# LR3.net
KiCad netlist of a schematic drawn in EasyEDA
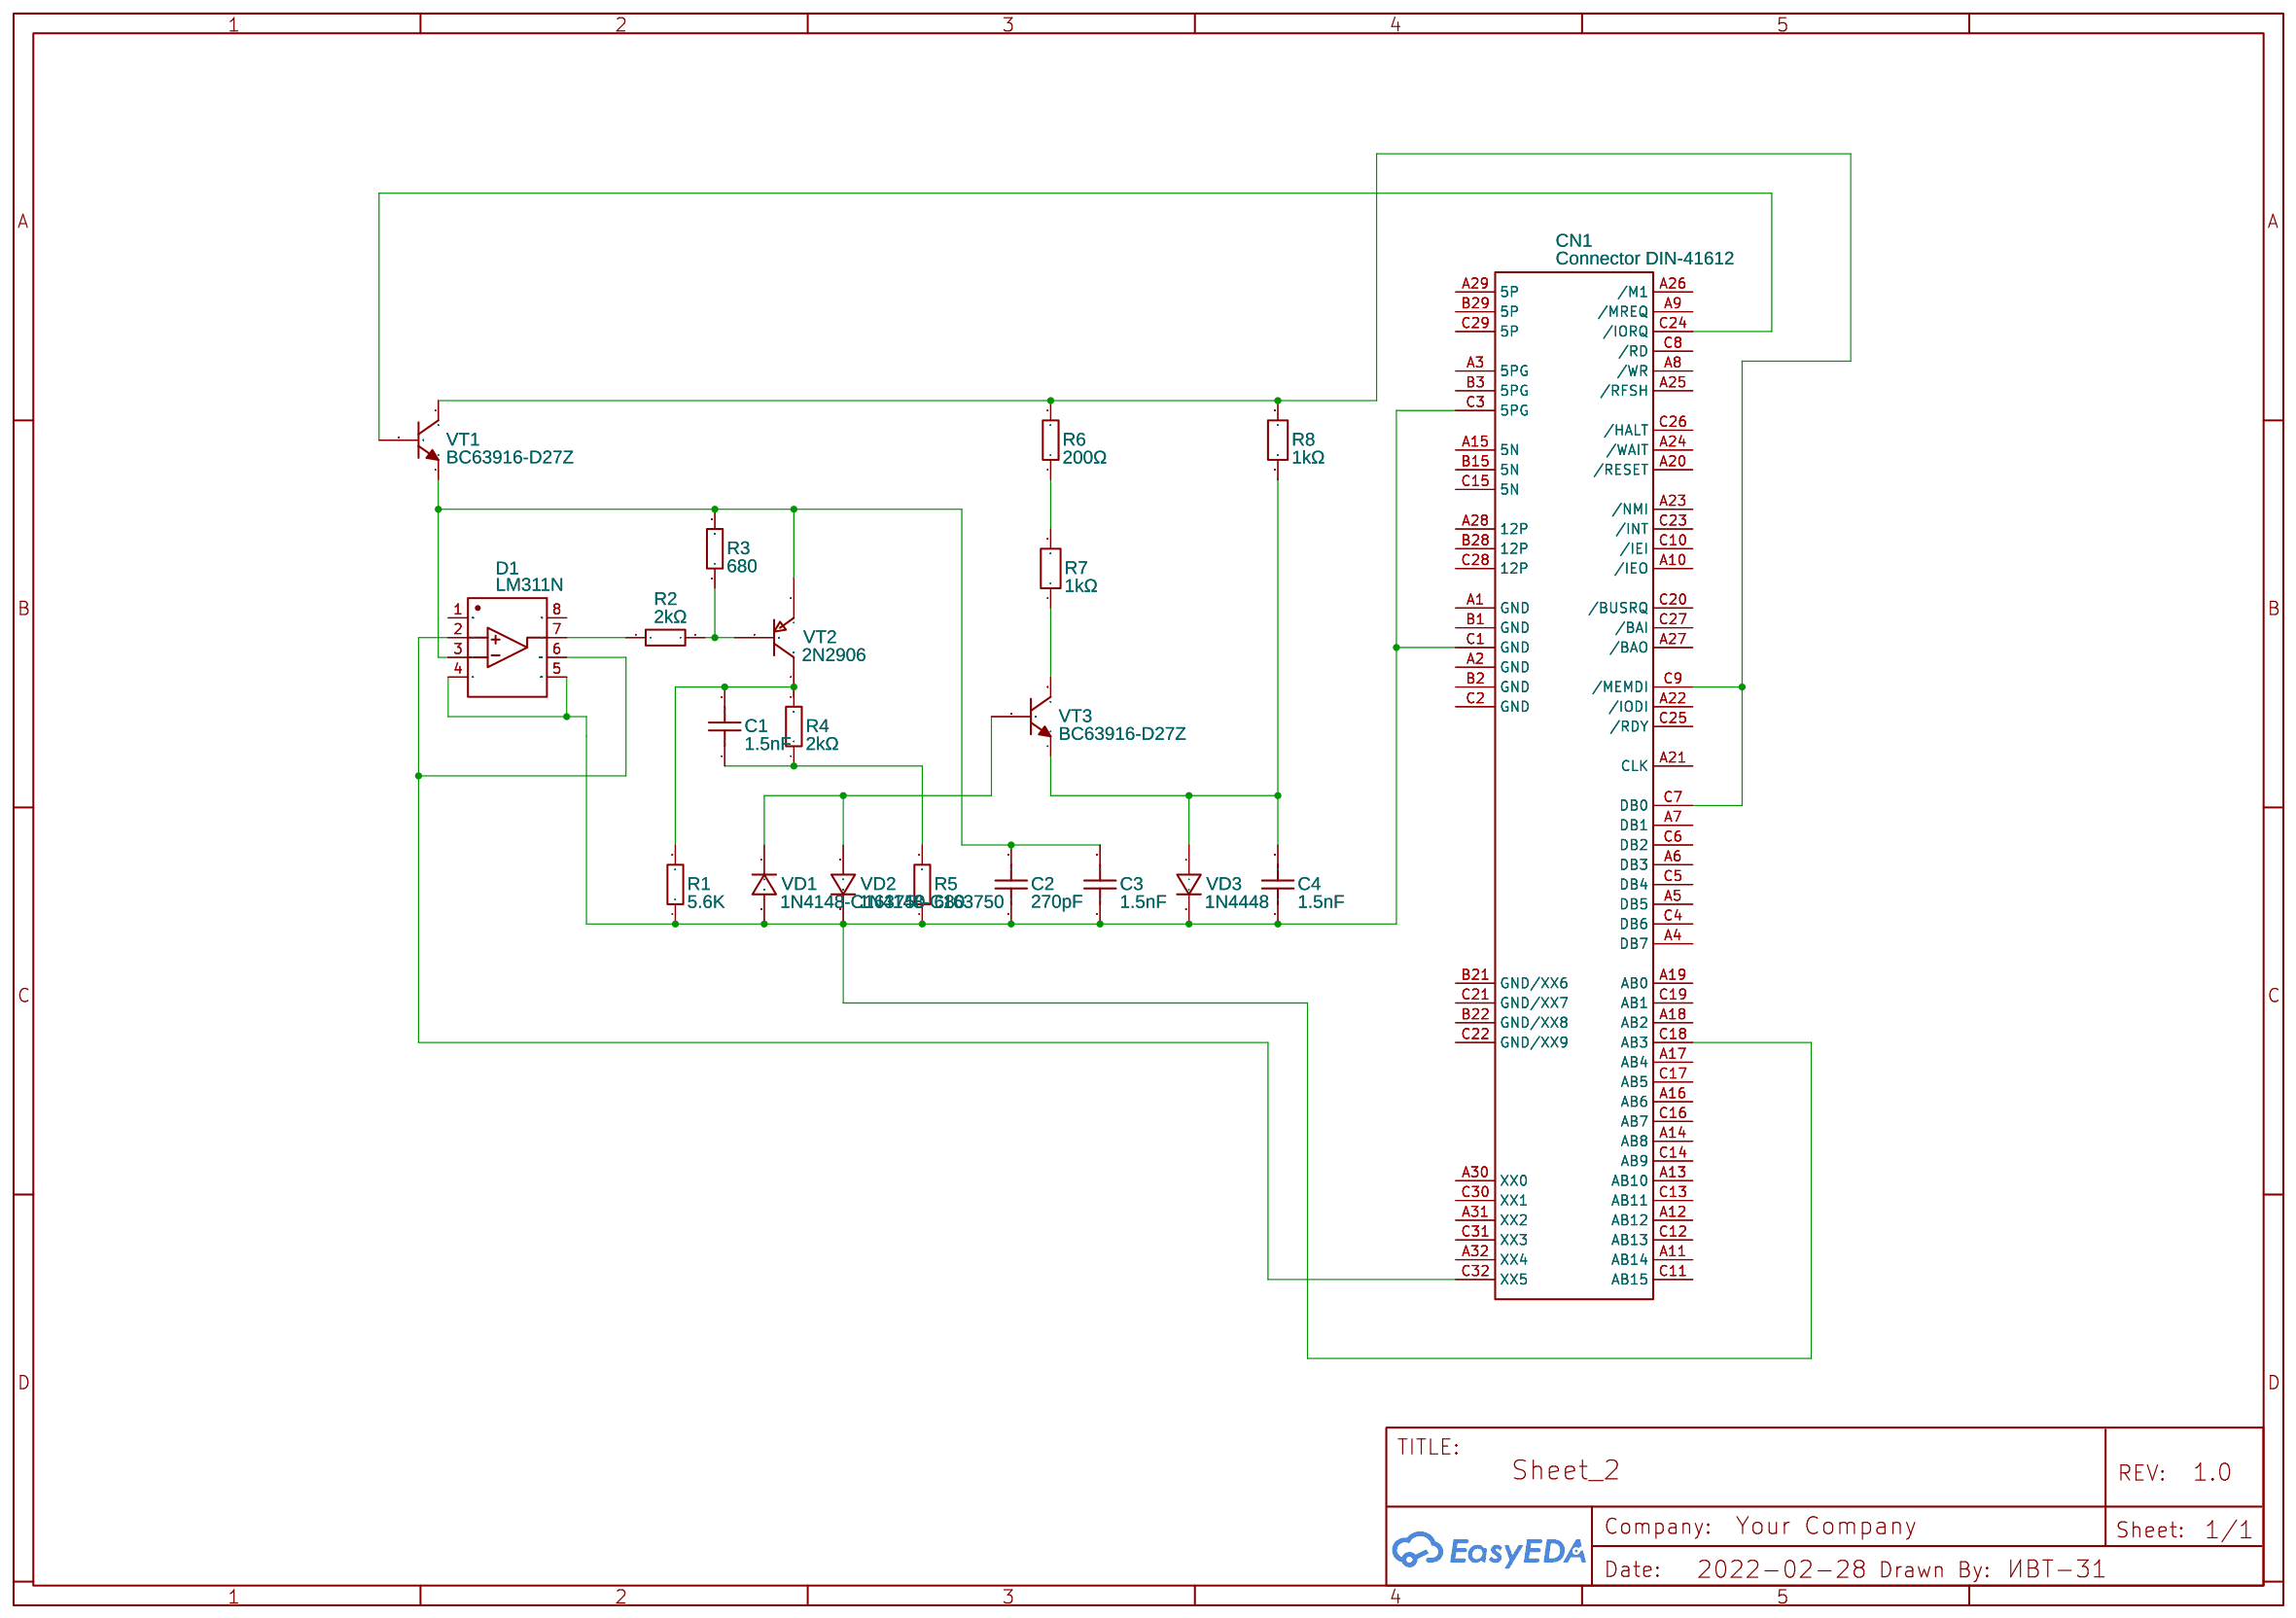
[diagram p0: schematic sheet]

(export (version "E")
  (design (tool "Eeschema 10.0.6"))
  (components
    (comp (ref "C1")
      (value "1.5nF")
      (fields
        (field (name "BOM_Manufacturer Part") "CK45-B3AD152KYVNA")
        (field (name "BOM_Supplier Part") "C342400")
      )
      (libsource (lib "") (part "CK45-B3AD152KYVNA"))
    )
    (comp (ref "C2")
      (value "270pF")
      (fields
        (field (name "BOM_Manufacturer Part") "CC1H271KC74DB44B10MN")
        (field (name "BOM_Supplier Part") "C254100")
      )
      (libsource (lib "") (part "CC1H271KC74DB44B10MN"))
    )
    (comp (ref "C3")
      (value "1.5nF")
      (fields
        (field (name "BOM_Manufacturer Part") "CK45-B3AD152KYVNA")
        (field (name "BOM_Supplier Part") "C342400")
      )
      (libsource (lib "") (part "CK45-B3AD152KYVNA"))
    )
    (comp (ref "C4")
      (value "1.5nF")
      (fields
        (field (name "BOM_Manufacturer Part") "CK45-B3AD152KYVNA")
        (field (name "BOM_Supplier Part") "C342400")
      )
      (libsource (lib "") (part "CK45-B3AD152KYVNA"))
    )
    (comp (ref "CN1")
      (value "Connector DIN-41612")
      (fields (field (name "BOM_Manufacturer Part") "EFS87"))
      (libsource (lib "") (part "Connector DIN-41612"))
    )
    (comp (ref "D1")
      (value "LM311N")
      (fields (field (name "BOM_Supplier Part") "C434572"))
      (libsource (lib "") (part "LM311N"))
    )
    (comp (ref "R1")
      (value "5.6K")
      (fields
        (field (name "BOM_Manufacturer Part") "RC0402JR-075K6L")
        (field (name "BOM_Supplier Part") "C137856")
      )
      (libsource (lib "") (part "RC0402JR-075K6L"))
    )
    (comp (ref "R2")
      (value "2kΩ")
      (fields
        (field (name "BOM_Manufacturer Part") "0603WAF2001T5E")
        (field (name "BOM_Supplier Part") "C22975")
      )
      (libsource (lib "") (part "0603WAF2001T5E_1"))
    )
    (comp (ref "R3")
      (value "680")
      (fields
        (field (name "BOM_Manufacturer Part") "RC0402JR-07680RL")
        (field (name "BOM_Supplier Part") "C137849")
      )
      (libsource (lib "") (part "RC0402JR-07680RL"))
    )
    (comp (ref "R4")
      (value "2kΩ")
      (fields
        (field (name "BOM_Manufacturer Part") "0603WAF2001T5E")
        (field (name "BOM_Supplier Part") "C22975")
      )
      (libsource (lib "") (part "0603WAF2001T5E"))
    )
    (comp (ref "R5")
      (value "680")
      (fields
        (field (name "BOM_Manufacturer Part") "RC0402JR-07680RL")
        (field (name "BOM_Supplier Part") "C137849")
      )
      (libsource (lib "") (part "RC0402JR-07680RL"))
    )
    (comp (ref "R6")
      (value "200Ω")
      (fields
        (field (name "BOM_Manufacturer Part") "RTT06201JTP")
        (field (name "BOM_Supplier Part") "C104688")
      )
      (libsource (lib "") (part "RTT06201JTP"))
    )
    (comp (ref "R7")
      (value "1kΩ")
      (fields
        (field (name "BOM_Manufacturer Part") "AS05W2J0102T5E")
        (field (name "BOM_Supplier Part") "C560481")
      )
      (libsource (lib "") (part "AS05W2J0102T5E"))
    )
    (comp (ref "R8")
      (value "1kΩ")
      (fields
        (field (name "BOM_Manufacturer Part") "AS05W2J0102T5E")
        (field (name "BOM_Supplier Part") "C560481")
      )
      (libsource (lib "") (part "AS05W2J0102T5E"))
    )
    (comp (ref "VD1")
      (value "1N4148-C163750")
      (fields (field (name "BOM_Manufacturer Part") "1N4148") (field (name "BOM_Supplier Part") "C163750"))
      (libsource (lib "") (part "1N4148-C163750"))
    )
    (comp (ref "VD2")
      (value "1N4148-C163750")
      (fields (field (name "BOM_Manufacturer Part") "1N4148") (field (name "BOM_Supplier Part") "C163750"))
      (libsource (lib "") (part "1N4148-C163750_1"))
    )
    (comp (ref "VD3")
      (value "1N4448")
      (fields (field (name "BOM_Supplier Part") "C54037"))
      (libsource (lib "") (part "1N4448"))
    )
    (comp (ref "VT1")
      (value "BC63916-D27Z")
      (fields (field (name "BOM_Supplier Part") "C900812"))
      (libsource (lib "") (part "BC63916-D27Z"))
    )
    (comp (ref "VT2") (value "2N2906") (libsource (lib "") (part "2N2906")))
    (comp (ref "VT3")
      (value "BC63916-D27Z")
      (fields (field (name "BOM_Supplier Part") "C900812"))
      (libsource (lib "") (part "BC63916-D27Z"))
    )
  )
  (nets
    (net (code "1") (name "Net-(C1-Pad1)") (class "Default")
      (node (ref "C1") (pin "1") (pinfunction "1_1") (pintype "unspecified"))
      (node (ref "R4") (pin "1") (pinfunction "1_1") (pintype "input"))
      (node (ref "R5") (pin "2") (pinfunction "2_2") (pintype "input"))
    )
    (net (code "2") (name "Net-(C1-Pad2)") (class "Default")
      (node (ref "C1") (pin "2") (pinfunction "2_2") (pintype "unspecified"))
      (node (ref "R1") (pin "2") (pinfunction "2_2") (pintype "input"))
      (node (ref "R4") (pin "2") (pinfunction "2_2") (pintype "input"))
    )
    (net (code "3") (name "Net-(CN1-AB3)") (class "Default")
      (node (ref "C2") (pin "1") (pinfunction "1_1") (pintype "unspecified"))
      (node (ref "C3") (pin "1") (pinfunction "1_1") (pintype "unspecified"))
      (node (ref "C4") (pin "1") (pinfunction "1_1") (pintype "unspecified"))
      (node (ref "CN1") (pin "C1") (pinfunction "GND_C1") (pintype "unspecified"))
      (node (ref "CN1") (pin "C18") (pinfunction "AB3_C18") (pintype "unspecified"))
      (node (ref "CN1") (pin "C3") (pinfunction "5PG_C3") (pintype "unspecified"))
      (node (ref "D1") (pin "4") (pinfunction "VEE_4") (pintype "unspecified"))
      (node (ref "D1") (pin "5") (pinfunction "BALANCE_5") (pintype "unspecified"))
      (node (ref "R1") (pin "1") (pinfunction "1_1") (pintype "input"))
      (node (ref "R5") (pin "1") (pinfunction "1_1") (pintype "input"))
      (node (ref "VD1") (pin "2") (pinfunction "2_2") (pintype "unspecified"))
      (node (ref "VD2") (pin "1") (pinfunction "1_1") (pintype "unspecified"))
      (node (ref "VD3") (pin "2") (pinfunction "K_2") (pintype "unspecified"))
    )
    (net (code "4") (name "Net-(CN1-DB0)") (class "Default")
      (node (ref "CN1") (pin "C7") (pinfunction "DB0_C7") (pintype "unspecified"))
      (node (ref "CN1") (pin "C9") (pinfunction "/MEMDI_C9") (pintype "unspecified"))
      (node (ref "R6") (pin "2") (pinfunction "2_2") (pintype "input"))
      (node (ref "R8") (pin "2") (pinfunction "2_2") (pintype "unspecified"))
      (node (ref "VT1") (pin "2") (pinfunction "C_2") (pintype "unspecified"))
    )
    (net (code "5") (name "Net-(CN1-XX5)") (class "Default")
      (node (ref "CN1") (pin "C32") (pinfunction "XX5_C32") (pintype "unspecified"))
      (node (ref "D1") (pin "2") (pinfunction "IN+_2") (pintype "unspecified"))
      (node (ref "D1") (pin "6") (pinfunction "BALANCE/STROBE_6") (pintype "unspecified"))
    )
    (net (code "6") (name "Net-(CN1-{slash}IORQ)") (class "Default")
      (node (ref "CN1") (pin "C24") (pinfunction "/IORQ_C24") (pintype "unspecified"))
      (node (ref "VT1") (pin "3") (pinfunction "B_3") (pintype "unspecified"))
    )
    (net (code "7") (name "Net-(D1-IN-)") (class "Default")
      (node (ref "C2") (pin "2") (pinfunction "2_2") (pintype "unspecified"))
      (node (ref "C3") (pin "2") (pinfunction "2_2") (pintype "unspecified"))
      (node (ref "D1") (pin "3") (pinfunction "IN-_3") (pintype "unspecified"))
      (node (ref "R3") (pin "2") (pinfunction "2_2") (pintype "input"))
      (node (ref "VT1") (pin "1") (pinfunction "E_1") (pintype "unspecified"))
      (node (ref "VT2") (pin "1") (pinfunction "E_1") (pintype "unspecified"))
    )
    (net (code "8") (name "Net-(D1-OUT)") (class "Default")
      (node (ref "D1") (pin "7") (pinfunction "OUT_7") (pintype "unspecified"))
      (node (ref "R2") (pin "1") (pinfunction "1_1") (pintype "input"))
    )
    (net (code "9") (name "Net-(R6-Pad1)") (class "Default")
      (node (ref "R6") (pin "1") (pinfunction "1_1") (pintype "input"))
      (node (ref "R7") (pin "2") (pinfunction "2_2") (pintype "unspecified"))
    )
    (net (code "10") (name "Net-(VD3-A)") (class "Default")
      (node (ref "C4") (pin "2") (pinfunction "2_2") (pintype "unspecified"))
      (node (ref "R8") (pin "1") (pinfunction "1_1") (pintype "unspecified"))
      (node (ref "VD3") (pin "1") (pinfunction "A_1") (pintype "unspecified"))
      (node (ref "VT3") (pin "1") (pinfunction "E_1") (pintype "unspecified"))
    )
    (net (code "11") (name "Net-(VT2-B)") (class "Default")
      (node (ref "R2") (pin "2") (pinfunction "2_2") (pintype "input"))
      (node (ref "R3") (pin "1") (pinfunction "1_1") (pintype "input"))
      (node (ref "VT2") (pin "2") (pinfunction "B_2") (pintype "unspecified"))
    )
    (net (code "12") (name "Net-(VT3-B)") (class "Default")
      (node (ref "VD1") (pin "1") (pinfunction "1_1") (pintype "unspecified"))
      (node (ref "VD2") (pin "2") (pinfunction "2_2") (pintype "unspecified"))
      (node (ref "VT3") (pin "3") (pinfunction "B_3") (pintype "unspecified"))
    )
    (net (code "13") (name "Net-(VT3-C)") (class "Default")
      (node (ref "R7") (pin "1") (pinfunction "1_1") (pintype "unspecified"))
      (node (ref "VT3") (pin "2") (pinfunction "C_2") (pintype "unspecified"))
    )
    (net (code "14") (name "unconnected-(CN1-5N-PadA15)") (class "Default")
      (node (ref "CN1") (pin "A15") (pinfunction "5N_A15") (pintype "unspecified"))
    )
    (net (code "15") (name "unconnected-(CN1-5N-PadB15)") (class "Default")
      (node (ref "CN1") (pin "B15") (pinfunction "5N_B15") (pintype "unspecified"))
    )
    (net (code "16") (name "unconnected-(CN1-5N-PadC15)") (class "Default")
      (node (ref "CN1") (pin "C15") (pinfunction "5N_C15") (pintype "unspecified"))
    )
    (net (code "17") (name "unconnected-(CN1-5P-PadA29)") (class "Default")
      (node (ref "CN1") (pin "A29") (pinfunction "5P_A29") (pintype "unspecified"))
    )
    (net (code "18") (name "unconnected-(CN1-5P-PadB29)") (class "Default")
      (node (ref "CN1") (pin "B29") (pinfunction "5P_B29") (pintype "unspecified"))
    )
    (net (code "19") (name "unconnected-(CN1-5P-PadC29)") (class "Default")
      (node (ref "CN1") (pin "C29") (pinfunction "5P_C29") (pintype "unspecified"))
    )
    (net (code "20") (name "unconnected-(CN1-5PG-PadA3)") (class "Default")
      (node (ref "CN1") (pin "A3") (pinfunction "5PG_A3") (pintype "unspecified"))
    )
    (net (code "21") (name "unconnected-(CN1-5PG-PadB3)") (class "Default")
      (node (ref "CN1") (pin "B3") (pinfunction "5PG_B3") (pintype "unspecified"))
    )
    (net (code "22") (name "unconnected-(CN1-12P-PadA28)") (class "Default")
      (node (ref "CN1") (pin "A28") (pinfunction "12P_A28") (pintype "unspecified"))
    )
    (net (code "23") (name "unconnected-(CN1-12P-PadB28)") (class "Default")
      (node (ref "CN1") (pin "B28") (pinfunction "12P_B28") (pintype "unspecified"))
    )
    (net (code "24") (name "unconnected-(CN1-12P-PadC28)") (class "Default")
      (node (ref "CN1") (pin "C28") (pinfunction "12P_C28") (pintype "unspecified"))
    )
    (net (code "25") (name "unconnected-(CN1-AB0-PadA19)") (class "Default")
      (node (ref "CN1") (pin "A19") (pinfunction "AB0_A19") (pintype "unspecified"))
    )
    (net (code "26") (name "unconnected-(CN1-AB1-PadC19)") (class "Default")
      (node (ref "CN1") (pin "C19") (pinfunction "AB1_C19") (pintype "unspecified"))
    )
    (net (code "27") (name "unconnected-(CN1-AB2-PadA18)") (class "Default")
      (node (ref "CN1") (pin "A18") (pinfunction "AB2_A18") (pintype "unspecified"))
    )
    (net (code "28") (name "unconnected-(CN1-AB4-PadA17)") (class "Default")
      (node (ref "CN1") (pin "A17") (pinfunction "AB4_A17") (pintype "unspecified"))
    )
    (net (code "29") (name "unconnected-(CN1-AB5-PadC17)") (class "Default")
      (node (ref "CN1") (pin "C17") (pinfunction "AB5_C17") (pintype "unspecified"))
    )
    (net (code "30") (name "unconnected-(CN1-AB6-PadA16)") (class "Default")
      (node (ref "CN1") (pin "A16") (pinfunction "AB6_A16") (pintype "unspecified"))
    )
    (net (code "31") (name "unconnected-(CN1-AB7-PadC16)") (class "Default")
      (node (ref "CN1") (pin "C16") (pinfunction "AB7_C16") (pintype "unspecified"))
    )
    (net (code "32") (name "unconnected-(CN1-AB8-PadA14)") (class "Default")
      (node (ref "CN1") (pin "A14") (pinfunction "AB8_A14") (pintype "unspecified"))
    )
    (net (code "33") (name "unconnected-(CN1-AB9-PadC14)") (class "Default")
      (node (ref "CN1") (pin "C14") (pinfunction "AB9_C14") (pintype "unspecified"))
    )
    (net (code "34") (name "unconnected-(CN1-AB10-PadA13)") (class "Default")
      (node (ref "CN1") (pin "A13") (pinfunction "AB10_A13") (pintype "unspecified"))
    )
    (net (code "35") (name "unconnected-(CN1-AB11-PadC13)") (class "Default")
      (node (ref "CN1") (pin "C13") (pinfunction "AB11_C13") (pintype "unspecified"))
    )
    (net (code "36") (name "unconnected-(CN1-AB12-PadA12)") (class "Default")
      (node (ref "CN1") (pin "A12") (pinfunction "AB12_A12") (pintype "unspecified"))
    )
    (net (code "37") (name "unconnected-(CN1-AB13-PadC12)") (class "Default")
      (node (ref "CN1") (pin "C12") (pinfunction "AB13_C12") (pintype "unspecified"))
    )
    (net (code "38") (name "unconnected-(CN1-AB14-PadA11)") (class "Default")
      (node (ref "CN1") (pin "A11") (pinfunction "AB14_A11") (pintype "unspecified"))
    )
    (net (code "39") (name "unconnected-(CN1-AB15-PadC11)") (class "Default")
      (node (ref "CN1") (pin "C11") (pinfunction "AB15_C11") (pintype "unspecified"))
    )
    (net (code "40") (name "unconnected-(CN1-CLK-PadA21)") (class "Default")
      (node (ref "CN1") (pin "A21") (pinfunction "CLK_A21") (pintype "unspecified"))
    )
    (net (code "41") (name "unconnected-(CN1-DB1-PadA7)") (class "Default")
      (node (ref "CN1") (pin "A7") (pinfunction "DB1_A7") (pintype "unspecified"))
    )
    (net (code "42") (name "unconnected-(CN1-DB2-PadC6)") (class "Default")
      (node (ref "CN1") (pin "C6") (pinfunction "DB2_C6") (pintype "unspecified"))
    )
    (net (code "43") (name "unconnected-(CN1-DB3-PadA6)") (class "Default")
      (node (ref "CN1") (pin "A6") (pinfunction "DB3_A6") (pintype "unspecified"))
    )
    (net (code "44") (name "unconnected-(CN1-DB4-PadC5)") (class "Default")
      (node (ref "CN1") (pin "C5") (pinfunction "DB4_C5") (pintype "unspecified"))
    )
    (net (code "45") (name "unconnected-(CN1-DB5-PadA5)") (class "Default")
      (node (ref "CN1") (pin "A5") (pinfunction "DB5_A5") (pintype "unspecified"))
    )
    (net (code "46") (name "unconnected-(CN1-DB6-PadC4)") (class "Default")
      (node (ref "CN1") (pin "C4") (pinfunction "DB6_C4") (pintype "unspecified"))
    )
    (net (code "47") (name "unconnected-(CN1-DB7-PadA4)") (class "Default")
      (node (ref "CN1") (pin "A4") (pinfunction "DB7_A4") (pintype "unspecified"))
    )
    (net (code "48") (name "unconnected-(CN1-GND-PadA1)") (class "Default")
      (node (ref "CN1") (pin "A1") (pinfunction "GND_A1") (pintype "unspecified"))
    )
    (net (code "49") (name "unconnected-(CN1-GND-PadA2)") (class "Default")
      (node (ref "CN1") (pin "A2") (pinfunction "GND_A2") (pintype "unspecified"))
    )
    (net (code "50") (name "unconnected-(CN1-GND-PadB1)") (class "Default")
      (node (ref "CN1") (pin "B1") (pinfunction "GND_B1") (pintype "unspecified"))
    )
    (net (code "51") (name "unconnected-(CN1-GND-PadB2)") (class "Default")
      (node (ref "CN1") (pin "B2") (pinfunction "GND_B2") (pintype "unspecified"))
    )
    (net (code "52") (name "unconnected-(CN1-GND-PadC2)") (class "Default")
      (node (ref "CN1") (pin "C2") (pinfunction "GND_C2") (pintype "unspecified"))
    )
    (net (code "53") (name "unconnected-(CN1-GND{slash}XX6-PadB21)") (class "Default")
      (node (ref "CN1") (pin "B21") (pinfunction "GND/XX6_B21") (pintype "unspecified"))
    )
    (net (code "54") (name "unconnected-(CN1-GND{slash}XX7-PadC21)") (class "Default")
      (node (ref "CN1") (pin "C21") (pinfunction "GND/XX7_C21") (pintype "unspecified"))
    )
    (net (code "55") (name "unconnected-(CN1-GND{slash}XX8-PadB22)") (class "Default")
      (node (ref "CN1") (pin "B22") (pinfunction "GND/XX8_B22") (pintype "unspecified"))
    )
    (net (code "56") (name "unconnected-(CN1-GND{slash}XX9-PadC22)") (class "Default")
      (node (ref "CN1") (pin "C22") (pinfunction "GND/XX9_C22") (pintype "unspecified"))
    )
    (net (code "57") (name "unconnected-(CN1-XX0-PadA30)") (class "Default")
      (node (ref "CN1") (pin "A30") (pinfunction "XX0_A30") (pintype "unspecified"))
    )
    (net (code "58") (name "unconnected-(CN1-XX1-PadC30)") (class "Default")
      (node (ref "CN1") (pin "C30") (pinfunction "XX1_C30") (pintype "unspecified"))
    )
    (net (code "59") (name "unconnected-(CN1-XX2-PadA31)") (class "Default")
      (node (ref "CN1") (pin "A31") (pinfunction "XX2_A31") (pintype "unspecified"))
    )
    (net (code "60") (name "unconnected-(CN1-XX3-PadC31)") (class "Default")
      (node (ref "CN1") (pin "C31") (pinfunction "XX3_C31") (pintype "unspecified"))
    )
    (net (code "61") (name "unconnected-(CN1-XX4-PadA32)") (class "Default")
      (node (ref "CN1") (pin "A32") (pinfunction "XX4_A32") (pintype "unspecified"))
    )
    (net (code "62") (name "unconnected-(CN1-{slash}BAI-PadC27)") (class "Default")
      (node (ref "CN1") (pin "C27") (pinfunction "/BAI_C27") (pintype "unspecified"))
    )
    (net (code "63") (name "unconnected-(CN1-{slash}BAO-PadA27)") (class "Default")
      (node (ref "CN1") (pin "A27") (pinfunction "/BAO_A27") (pintype "unspecified"))
    )
    (net (code "64") (name "unconnected-(CN1-{slash}BUSRQ-PadC20)") (class "Default")
      (node (ref "CN1") (pin "C20") (pinfunction "/BUSRQ_C20") (pintype "unspecified"))
    )
    (net (code "65") (name "unconnected-(CN1-{slash}HALT-PadC26)") (class "Default")
      (node (ref "CN1") (pin "C26") (pinfunction "/HALT_C26") (pintype "unspecified"))
    )
    (net (code "66") (name "unconnected-(CN1-{slash}IEI-PadC10)") (class "Default")
      (node (ref "CN1") (pin "C10") (pinfunction "/IEI_C10") (pintype "unspecified"))
    )
    (net (code "67") (name "unconnected-(CN1-{slash}IEO-PadA10)") (class "Default")
      (node (ref "CN1") (pin "A10") (pinfunction "/IEO_A10") (pintype "unspecified"))
    )
    (net (code "68") (name "unconnected-(CN1-{slash}INT-PadC23)") (class "Default")
      (node (ref "CN1") (pin "C23") (pinfunction "/INT_C23") (pintype "unspecified"))
    )
    (net (code "69") (name "unconnected-(CN1-{slash}IODI-PadA22)") (class "Default")
      (node (ref "CN1") (pin "A22") (pinfunction "/IODI_A22") (pintype "unspecified"))
    )
    (net (code "70") (name "unconnected-(CN1-{slash}M1-PadA26)") (class "Default")
      (node (ref "CN1") (pin "A26") (pinfunction "/M1_A26") (pintype "unspecified"))
    )
    (net (code "71") (name "unconnected-(CN1-{slash}MREQ-PadA9)") (class "Default")
      (node (ref "CN1") (pin "A9") (pinfunction "/MREQ_A9") (pintype "unspecified"))
    )
    (net (code "72") (name "unconnected-(CN1-{slash}NMI-PadA23)") (class "Default")
      (node (ref "CN1") (pin "A23") (pinfunction "/NMI_A23") (pintype "unspecified"))
    )
    (net (code "73") (name "unconnected-(CN1-{slash}RD-PadC8)") (class "Default")
      (node (ref "CN1") (pin "C8") (pinfunction "/RD_C8") (pintype "unspecified"))
    )
    (net (code "74") (name "unconnected-(CN1-{slash}RDY-PadC25)") (class "Default")
      (node (ref "CN1") (pin "C25") (pinfunction "/RDY_C25") (pintype "unspecified"))
    )
    (net (code "75") (name "unconnected-(CN1-{slash}RESET-PadA20)") (class "Default")
      (node (ref "CN1") (pin "A20") (pinfunction "/RESET_A20") (pintype "unspecified"))
    )
    (net (code "76") (name "unconnected-(CN1-{slash}RFSH-PadA25)") (class "Default")
      (node (ref "CN1") (pin "A25") (pinfunction "/RFSH_A25") (pintype "unspecified"))
    )
    (net (code "77") (name "unconnected-(CN1-{slash}WAIT-PadA24)") (class "Default")
      (node (ref "CN1") (pin "A24") (pinfunction "/WAIT_A24") (pintype "unspecified"))
    )
    (net (code "78") (name "unconnected-(CN1-{slash}WR-PadA8)") (class "Default")
      (node (ref "CN1") (pin "A8") (pinfunction "/WR_A8") (pintype "unspecified"))
    )
    (net (code "79") (name "unconnected-(D1-GND-Pad1)") (class "Default")
      (node (ref "D1") (pin "1") (pinfunction "GND_1") (pintype "unspecified"))
    )
    (net (code "80") (name "unconnected-(D1-VCC-Pad8)") (class "Default")
      (node (ref "D1") (pin "8") (pinfunction "VCC_8") (pintype "unspecified"))
    )
    (net (code "81") (name "unconnected-(VT2-C-Pad3)") (class "Default")
      (node (ref "VT2") (pin "3") (pinfunction "C_3") (pintype "unspecified"))
    )
  )
)
